# ppmacboard.net
KiCad netlist of a schematic drawn in EAGLE
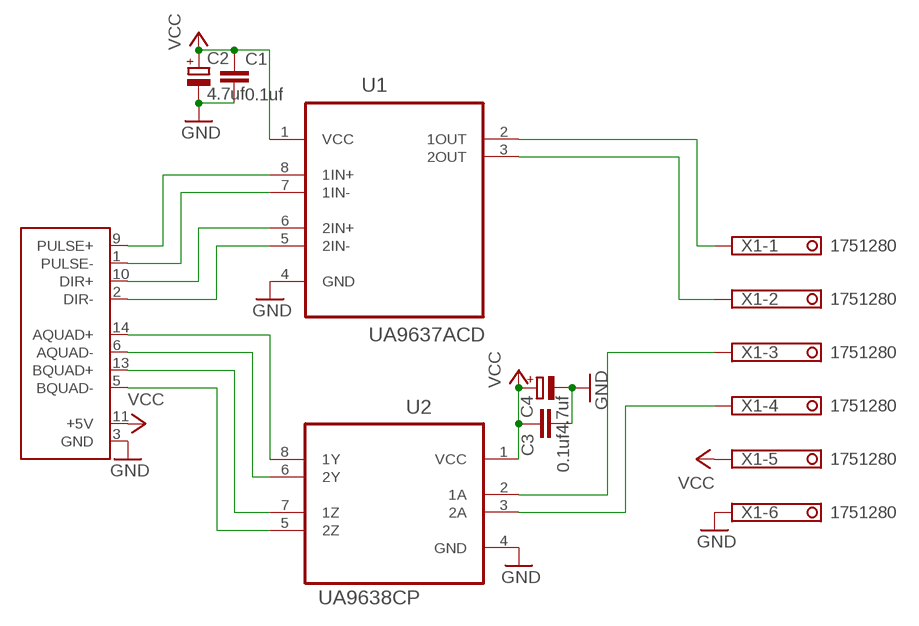
[diagram p0: schematic, sheet 1]

(export (version "E")
  (design (tool "Eeschema 10.0.6"))
  (components
    (comp (ref "C1")
      (value "0.1uf")
      (footprint "eagle-import:C1206")
      (fields (field (name "PARTNO") "C1206C104K3RACTU"))
      (libsource (lib "eagle-import") (part "C-EUC1206"))
    )
    (comp (ref "C2")
      (value "4.7uf")
      (footprint "eagle-import:A_3216-18W")
      (fields (field (name "PARTNO") "T491A475M025AT"))
      (libsource (lib "eagle-import") (part "CPOL-EUA/3216-18W"))
    )
    (comp (ref "C3")
      (value "0.1uf")
      (footprint "eagle-import:C1206")
      (fields (field (name "PARTNO") "C1206C104K3RACTU"))
      (libsource (lib "eagle-import") (part "C-EUC1206"))
    )
    (comp (ref "C4")
      (value "4.7uf")
      (footprint "eagle-import:A_3216-18W")
      (fields (field (name "PARTNO") "T491A475M025AT"))
      (libsource (lib "eagle-import") (part "CPOL-EUA/3216-18W"))
    )
    (comp (ref "U$1")
      (value "AFBPUQUOUT")
      (footprint "eagle-import:M15HP")
      (libsource (lib "eagle-import") (part "AFBPUQUOUT"))
    )
    (comp (ref "U1")
      (value "UA9637ACD")
      (footprint "eagle-import:SOIC127P600X175-8N")
      (libsource (lib "eagle-import") (part "UA9637ACD"))
    )
    (comp (ref "U2")
      (value "UA9638CP")
      (footprint "eagle-import:SOIC127P600X272-8N")
      (libsource (lib "eagle-import") (part "UA9638CP"))
    )
    (comp (ref "X1")
      (value "1751280")
      (footprint "eagle-import:1751280")
      (libsource (lib "eagle-import") (part "1751280"))
    )
  )
  (nets
    (net (code "1") (name "GND") (class "Default")
      (node (ref "C1") (pin "2") (pinfunction "2_2") (pintype "passive"))
      (node (ref "C2") (pin "-") (pinfunction "-_-") (pintype "passive"))
      (node (ref "C3") (pin "2") (pinfunction "2_2") (pintype "passive"))
      (node (ref "C4") (pin "-") (pinfunction "-_-") (pintype "passive"))
      (node (ref "U$1") (pin "3") (pinfunction "GND_3") (pintype "power_in"))
      (node (ref "U1") (pin "4") (pinfunction "GND_4") (pintype "passive"))
      (node (ref "U2") (pin "4") (pinfunction "GND_4") (pintype "passive"))
      (node (ref "X1") (pin "6") (pinfunction "K_6") (pintype "passive"))
    )
    (net (code "2") (name "Net-(U$1-AQUAD+)") (class "Default")
      (node (ref "U$1") (pin "14") (pinfunction "AQUAD+_14") (pintype "input"))
      (node (ref "U2") (pin "8") (pinfunction "1Y_8") (pintype "output"))
    )
    (net (code "3") (name "Net-(U$1-AQUAD-)") (class "Default")
      (node (ref "U$1") (pin "6") (pinfunction "AQUAD-_6") (pintype "input"))
      (node (ref "U2") (pin "6") (pinfunction "2Y_6") (pintype "output"))
    )
    (net (code "4") (name "Net-(U$1-BQUAD+)") (class "Default")
      (node (ref "U$1") (pin "13") (pinfunction "BQUAD+_13") (pintype "input"))
      (node (ref "U2") (pin "7") (pinfunction "1Z_7") (pintype "output"))
    )
    (net (code "5") (name "Net-(U$1-BQUAD-)") (class "Default")
      (node (ref "U$1") (pin "5") (pinfunction "BQUAD-_5") (pintype "bidirectional"))
      (node (ref "U2") (pin "5") (pinfunction "2Z_5") (pintype "output"))
    )
    (net (code "6") (name "Net-(U$1-DIR+)") (class "Default")
      (node (ref "U$1") (pin "10") (pinfunction "DIR+_10") (pintype "output"))
      (node (ref "U1") (pin "6") (pinfunction "2IN+_6") (pintype "input"))
    )
    (net (code "7") (name "Net-(U$1-DIR-)") (class "Default")
      (node (ref "U$1") (pin "2") (pinfunction "DIR-_2") (pintype "output"))
      (node (ref "U1") (pin "5") (pinfunction "2IN-_5") (pintype "input"))
    )
    (net (code "8") (name "Net-(U$1-PULSE+)") (class "Default")
      (node (ref "U$1") (pin "9") (pinfunction "PULSE+_9") (pintype "output"))
      (node (ref "U1") (pin "8") (pinfunction "1IN+_8") (pintype "input"))
    )
    (net (code "9") (name "Net-(U$1-PULSE-)") (class "Default")
      (node (ref "U$1") (pin "1") (pinfunction "PULSE-_1") (pintype "output"))
      (node (ref "U1") (pin "7") (pinfunction "1IN-_7") (pintype "input"))
    )
    (net (code "10") (name "Net-(U1-1OUT)") (class "Default")
      (node (ref "U1") (pin "2") (pinfunction "1OUT_2") (pintype "output"))
      (node (ref "X1") (pin "1") (pinfunction "K_1") (pintype "passive"))
    )
    (net (code "11") (name "Net-(U1-2OUT)") (class "Default")
      (node (ref "U1") (pin "3") (pinfunction "2OUT_3") (pintype "output"))
      (node (ref "X1") (pin "2") (pinfunction "K_2") (pintype "passive"))
    )
    (net (code "12") (name "Net-(U2-1A)") (class "Default")
      (node (ref "U2") (pin "2") (pinfunction "1A_2") (pintype "input"))
      (node (ref "X1") (pin "3") (pinfunction "K_3") (pintype "passive"))
    )
    (net (code "13") (name "Net-(U2-2A)") (class "Default")
      (node (ref "U2") (pin "3") (pinfunction "2A_3") (pintype "input"))
      (node (ref "X1") (pin "4") (pinfunction "K_4") (pintype "passive"))
    )
    (net (code "14") (name "VCC") (class "Default")
      (node (ref "C1") (pin "1") (pinfunction "1_1") (pintype "passive"))
      (node (ref "C2") (pin "+") (pinfunction "+_+") (pintype "passive"))
      (node (ref "C3") (pin "1") (pinfunction "1_1") (pintype "passive"))
      (node (ref "C4") (pin "+") (pinfunction "+_+") (pintype "passive"))
      (node (ref "U$1") (pin "11") (pinfunction "+5V_11") (pintype "power_in"))
      (node (ref "U1") (pin "1") (pinfunction "VCC_1") (pintype "power_in"))
      (node (ref "U2") (pin "1") (pinfunction "VCC_1") (pintype "power_in"))
      (node (ref "X1") (pin "5") (pinfunction "K_5") (pintype "passive"))
    )
  )
)
